# USB.net
KiCad netlist of a schematic drawn in Altium Designer
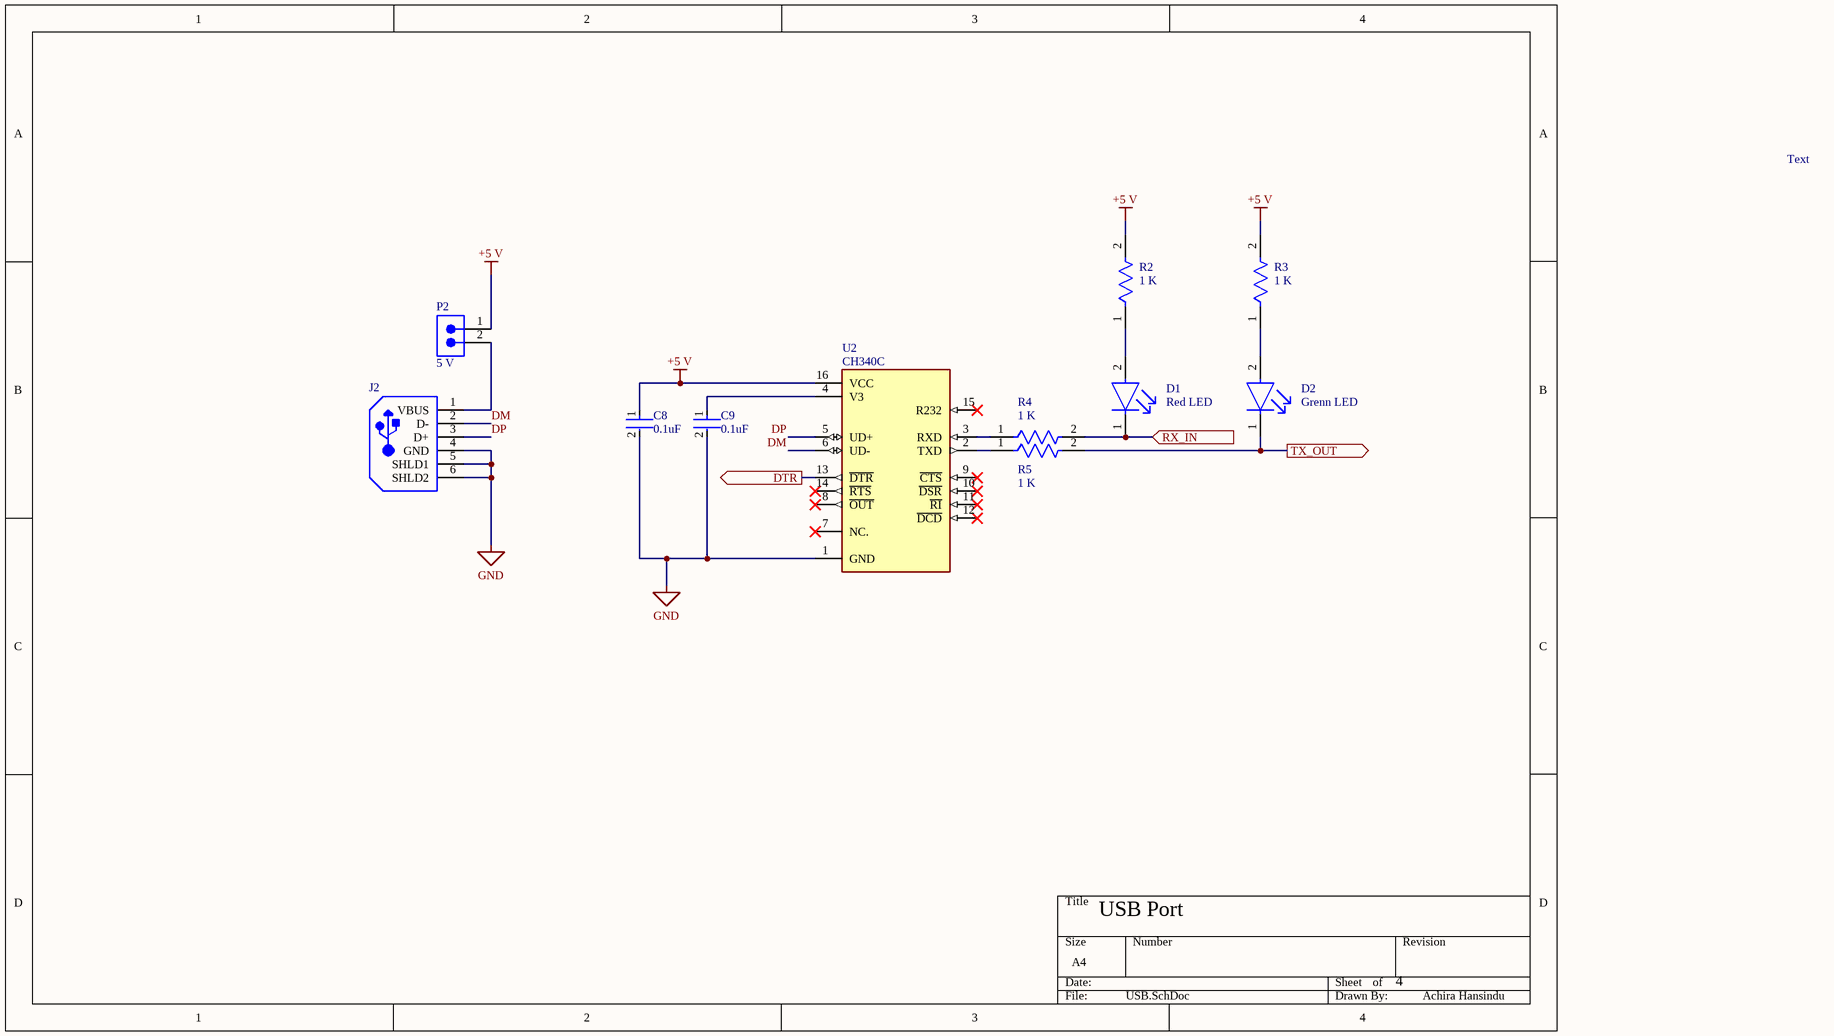
[diagram p0: USB.SchDoc]

(export (version "E")
  (design (tool "Eeschema 10.0.6"))
  (components
    (comp (ref "C8")
      (value "GRM31M1X1H104JA01L")
      (footprint "FP-GRM31M-0_15-IPC_A")
      (fields
        (field (name "VOLTAGE") "50V")
        (field (name "TOLERANCE") "5%")
        (field (name "CAPACITANCE") "0.1uF")
      )
      (libsource (lib "Altium Content Vault") (part "b4654b650e69147ec39a6b967a45e02"))
    )
    (comp (ref "C9")
      (value "GRM31M1X1H104JA01L")
      (footprint "FP-GRM31M-0_15-IPC_A")
      (fields
        (field (name "VOLTAGE") "50V")
        (field (name "TOLERANCE") "5%")
        (field (name "CAPACITANCE") "0.1uF")
      )
      (libsource (lib "Altium Content Vault") (part "b4654b650e69147ec39a6b967a45e02"))
    )
    (comp (ref "D1")
      (value "HSMG-C150")
      (footprint "FP-HSMG-C150-MFG")
      (description "LED GREEN DIFFUSED 1206 SMD")
      (fields
        (field (name "MANUFACTURER") "Broadcom")
        (field (name "OCTOPART") "https://octopart.com/hsmg-c150-broadcom-71131304")
        (field (name "COLOR") "Red LED")
      )
      (libsource (lib "Altium Content Vault") (part "8706943c75ba83719d021d2fdc84c58"))
    )
    (comp (ref "D2")
      (value "HSMG-C150")
      (footprint "FP-HSMG-C150-MFG")
      (description "LED GREEN DIFFUSED 1206 SMD")
      (fields
        (field (name "MANUFACTURER") "Broadcom")
        (field (name "OCTOPART") "https://octopart.com/hsmg-c150-broadcom-71131304")
        (field (name "COLOR") "Grenn LED")
      )
      (libsource (lib "Altium Content Vault") (part "8706943c75ba83719d021d2fdc84c58"))
    )
    (comp (ref "J2")
      (value "292303-1")
      (footprint "TE-292303-1_V")
      (fields (field (name "MANUFACTURER") "TE Connectivity"))
      (libsource (lib "Altium Content Vault") (part "USB-4-2SHLD"))
    )
    (comp (ref "P2")
      (value "5 V")
      (footprint "691322110002")
      (fields (field (name "VOLTAGE") "300V"))
      (libsource (lib "Altium Content Vault") (part "TBL - 1R - 02P - Male"))
    )
    (comp (ref "R2")
      (value "1 K")
      (footprint "FP-CHP1206A-MFG")
      (description "RESHIGHPOWERA 1206 1K 1% 3/4W TC")
      (fields (field (name "Comment") "CHP1206AFX-1001ELF"))
      (libsource (lib "Altium Content Vault") (part "1029c3af85768c4190bb7ad29bc67b5"))
    )
    (comp (ref "R3")
      (value "1 K")
      (footprint "FP-CHP1206A-MFG")
      (description "RESHIGHPOWERA 1206 1K 1% 3/4W TC")
      (fields (field (name "Comment") "CHP1206AFX-1001ELF"))
      (libsource (lib "Altium Content Vault") (part "1029c3af85768c4190bb7ad29bc67b5"))
    )
    (comp (ref "R4")
      (value "1 K")
      (footprint "FP-CHP1206A-MFG")
      (description "RESHIGHPOWERA 1206 1K 1% 3/4W TC")
      (fields (field (name "Comment") "CHP1206AFX-1001ELF"))
      (libsource (lib "Altium Content Vault") (part "1029c3af85768c4190bb7ad29bc67b5"))
    )
    (comp (ref "R5")
      (value "1 K")
      (footprint "FP-CHP1206A-MFG")
      (description "RESHIGHPOWERA 1206 1K 1% 3/4W TC")
      (fields (field (name "Comment") "CHP1206AFX-1001ELF"))
      (libsource (lib "Altium Content Vault") (part "1029c3af85768c4190bb7ad29bc67b5"))
    )
    (comp (ref "U2")
      (value "CH340C")
      (footprint "SOIC127P600X180-16N")
      (description "USB to serial chip CH340")
      (fields (field (name "MF") "WCH"))
      (libsource (lib "CH340C (1)") (part "CH340C"))
    )
  )
  (nets
    (net (code "1") (name "+5 V") (class "Default")
      (node (ref "C8") (pin "1") (pinfunction "1_1") (pintype "passive"))
      (node (ref "P2") (pin "1") (pinfunction "1_1") (pintype "passive"))
      (node (ref "R2") (pin "2") (pinfunction "2_2") (pintype "passive"))
      (node (ref "R3") (pin "2") (pinfunction "2_2") (pintype "passive"))
      (node (ref "U2") (pin "16") (pinfunction "VCC_16") (pintype "power_in"))
    )
    (net (code "2") (name "/DM") (class "Default")
      (node (ref "J2") (pin "2") (pinfunction "D-_2") (pintype "passive"))
      (node (ref "U2") (pin "6") (pinfunction "UD-_6") (pintype "bidirectional"))
    )
    (net (code "3") (name "/DP") (class "Default")
      (node (ref "J2") (pin "3") (pinfunction "D+_3") (pintype "passive"))
      (node (ref "U2") (pin "5") (pinfunction "UD+_5") (pintype "bidirectional"))
    )
    (net (code "4") (name "/DTR") (class "Default")
      (node (ref "U2") (pin "13") (pinfunction "~{DTR}_13") (pintype "output"))
    )
    (net (code "5") (name "/RX_IN") (class "Default")
      (node (ref "D1") (pin "1") (pinfunction "C_1") (pintype "passive"))
      (node (ref "R4") (pin "2") (pinfunction "2_2") (pintype "passive"))
    )
    (net (code "6") (name "/TX_OUT") (class "Default")
      (node (ref "D2") (pin "1") (pinfunction "C_1") (pintype "passive"))
      (node (ref "R5") (pin "2") (pinfunction "2_2") (pintype "passive"))
    )
    (net (code "7") (name "GND") (class "Default")
      (node (ref "C8") (pin "2") (pinfunction "2_2") (pintype "passive"))
      (node (ref "C9") (pin "2") (pinfunction "2_2") (pintype "passive"))
      (node (ref "J2") (pin "4") (pinfunction "GND_4") (pintype "passive"))
      (node (ref "J2") (pin "5") (pinfunction "SHLD1_5") (pintype "passive"))
      (node (ref "J2") (pin "6") (pinfunction "SHLD2_6") (pintype "passive"))
      (node (ref "U2") (pin "1") (pinfunction "GND_1") (pintype "power_in"))
    )
    (net (code "8") (name "Net-(D1-A)") (class "Default")
      (node (ref "D1") (pin "2") (pinfunction "A_2") (pintype "passive"))
      (node (ref "R2") (pin "1") (pinfunction "1_1") (pintype "passive"))
    )
    (net (code "9") (name "Net-(D2-A)") (class "Default")
      (node (ref "D2") (pin "2") (pinfunction "A_2") (pintype "passive"))
      (node (ref "R3") (pin "1") (pinfunction "1_1") (pintype "passive"))
    )
    (net (code "10") (name "Net-(J2-VBUS)") (class "Default")
      (node (ref "J2") (pin "1") (pinfunction "VBUS_1") (pintype "passive"))
      (node (ref "P2") (pin "2") (pinfunction "2_2") (pintype "passive"))
    )
    (net (code "11") (name "Net-(U2-RXD)") (class "Default")
      (node (ref "R4") (pin "1") (pinfunction "1_1") (pintype "passive"))
      (node (ref "U2") (pin "3") (pinfunction "RXD_3") (pintype "input"))
    )
    (net (code "12") (name "Net-(U2-TXD)") (class "Default")
      (node (ref "R5") (pin "1") (pinfunction "1_1") (pintype "passive"))
      (node (ref "U2") (pin "2") (pinfunction "TXD_2") (pintype "output"))
    )
    (net (code "13") (name "Net-(U2-V3)") (class "Default")
      (node (ref "C9") (pin "1") (pinfunction "1_1") (pintype "passive"))
      (node (ref "U2") (pin "4") (pinfunction "V3_4") (pintype "power_in"))
    )
    (net (code "14") (name "unconnected-(U2-NC.-Pad7)") (class "Default")
      (node (ref "U2") (pin "7") (pinfunction "NC._7") (pintype "passive+no_connect"))
    )
    (net (code "15") (name "unconnected-(U2-R232-Pad15)") (class "Default")
      (node (ref "U2") (pin "15") (pinfunction "R232_15") (pintype "input+no_connect"))
    )
    (net (code "16") (name "unconnected-(U2-~{CTS}-Pad9)") (class "Default")
      (node (ref "U2") (pin "9") (pinfunction "~{CTS}_9") (pintype "input+no_connect"))
    )
    (net (code "17") (name "unconnected-(U2-~{DCD}-Pad12)") (class "Default")
      (node (ref "U2") (pin "12") (pinfunction "~{DCD}_12") (pintype "input+no_connect"))
    )
    (net (code "18") (name "unconnected-(U2-~{DSR}-Pad10)") (class "Default")
      (node (ref "U2") (pin "10") (pinfunction "~{DSR}_10") (pintype "input+no_connect"))
    )
    (net (code "19") (name "unconnected-(U2-~{OUT}-Pad8)") (class "Default")
      (node (ref "U2") (pin "8") (pinfunction "~{OUT}_8") (pintype "output+no_connect"))
    )
    (net (code "20") (name "unconnected-(U2-~{RI}-Pad11)") (class "Default")
      (node (ref "U2") (pin "11") (pinfunction "~{RI}_11") (pintype "input+no_connect"))
    )
    (net (code "21") (name "unconnected-(U2-~{RTS}-Pad14)") (class "Default")
      (node (ref "U2") (pin "14") (pinfunction "~{RTS}_14") (pintype "output+no_connect"))
    )
  )
)
